# SCH_Bullseye_ESP32_2022-06-18.net
KiCad netlist of a schematic drawn in EasyEDA
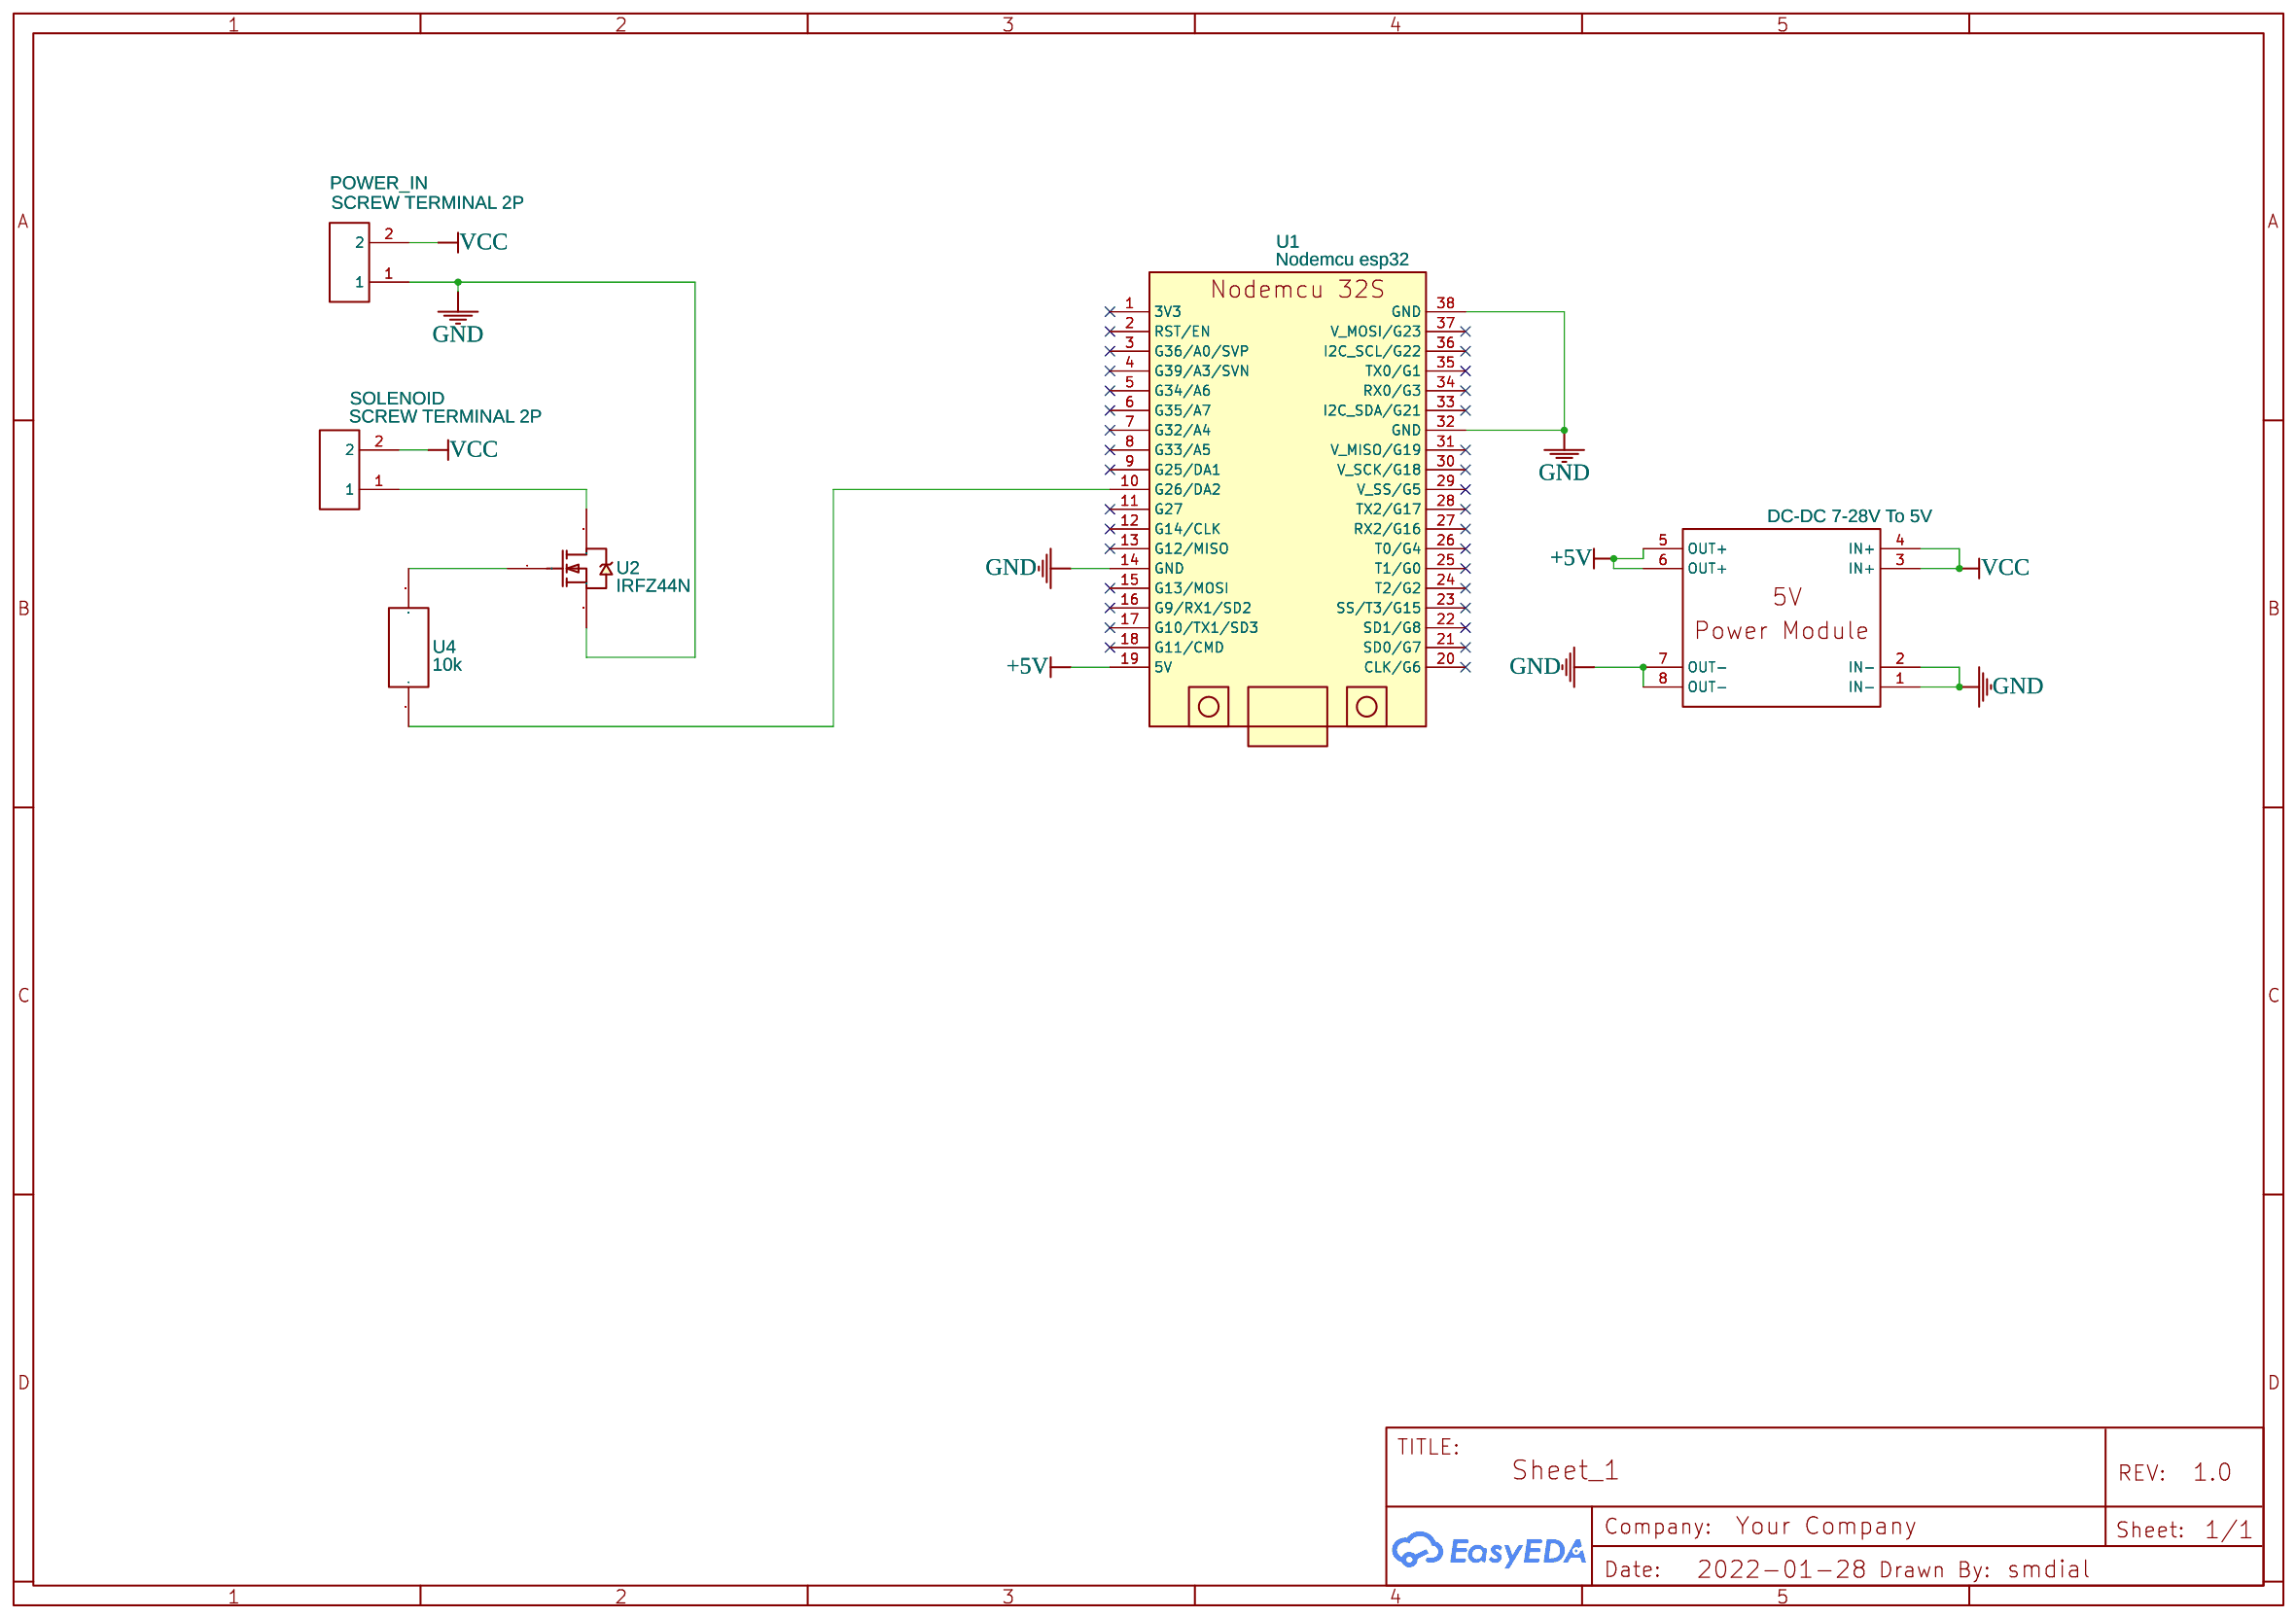
[diagram p0: schematic sheet]

(export (version "E")
  (design (tool "Eeschema 10.0.6"))
  (components
    (comp (ref "POWER_IN")
      (value "SCREW TERMINAL 2P")
      (fields (field (name "BOM_Manufacturer Part") "Screw terminal 2p"))
      (libsource (lib "") (part "SCREW TERMINAL 2P_1"))
    )
    (comp (ref "SOLENOID")
      (value "SCREW TERMINAL 2P")
      (fields (field (name "BOM_Manufacturer Part") "Screw terminal 2p"))
      (libsource (lib "") (part "SCREW TERMINAL 2P"))
    )
    (comp (ref "U1") (value "Nodemcu esp32") (libsource (lib "") (part "Nodemcu esp32")))
    (comp (ref "U2") (value "IRFZ44N") (libsource (lib "") (part "IRFZ44N")))
    (comp (ref "U3")
      (value "DC-DC 7-28V To 5V")
      (fields (field (name "BOM_Manufacturer Part") "DC-DC 7-28V To 5V Step Down Power Supply Module"))
      (libsource (lib "") (part "DC-DC 7-28V To 5V Step Down Power Supply Module"))
    )
    (comp (ref "U4") (value "10k") (libsource (lib "") (part "RESISTOR")))
  )
  (nets
    (net (code "1") (name "+5V") (class "Default")
      (node (ref "U1") (pin "19") (pinfunction "5V_19") (pintype "passive"))
      (node (ref "U3") (pin "5") (pinfunction "OUT+_5") (pintype "unspecified"))
      (node (ref "U3") (pin "6") (pinfunction "OUT+_6") (pintype "unspecified"))
    )
    (net (code "2") (name "GND") (class "Default")
      (node (ref "POWER_IN") (pin "1") (pinfunction "1_1") (pintype "unspecified"))
      (node (ref "U1") (pin "14") (pinfunction "GND_14") (pintype "passive"))
      (node (ref "U1") (pin "32") (pinfunction "GND_32") (pintype "passive"))
      (node (ref "U1") (pin "38") (pinfunction "GND_38") (pintype "passive"))
      (node (ref "U2") (pin "3") (pinfunction "S_3") (pintype "unspecified"))
      (node (ref "U3") (pin "1") (pinfunction "IN-_1") (pintype "unspecified"))
      (node (ref "U3") (pin "2") (pinfunction "IN-_2") (pintype "unspecified"))
      (node (ref "U3") (pin "7") (pinfunction "OUT-_7") (pintype "unspecified"))
      (node (ref "U3") (pin "8") (pinfunction "OUT-_8") (pintype "unspecified"))
    )
    (net (code "3") (name "Net-(U1-G26{slash}DA2)") (class "Default")
      (node (ref "U1") (pin "10") (pinfunction "G26/DA2_10") (pintype "bidirectional"))
      (node (ref "U4") (pin "1") (pinfunction "1_1") (pintype "unspecified"))
    )
    (net (code "4") (name "Net-(U2-D)") (class "Default")
      (node (ref "SOLENOID") (pin "1") (pinfunction "1_1") (pintype "unspecified"))
      (node (ref "U2") (pin "2") (pinfunction "D_2") (pintype "unspecified"))
    )
    (net (code "5") (name "Net-(U2-G)") (class "Default")
      (node (ref "U2") (pin "1") (pinfunction "G_1") (pintype "unspecified"))
      (node (ref "U4") (pin "2") (pinfunction "2_2") (pintype "unspecified"))
    )
    (net (code "6") (name "VCC") (class "Default")
      (node (ref "POWER_IN") (pin "2") (pinfunction "2_2") (pintype "unspecified"))
      (node (ref "SOLENOID") (pin "2") (pinfunction "2_2") (pintype "unspecified"))
      (node (ref "U3") (pin "3") (pinfunction "IN+_3") (pintype "unspecified"))
      (node (ref "U3") (pin "4") (pinfunction "IN+_4") (pintype "unspecified"))
    )
    (net (code "7") (name "unconnected-(U1-3V3-Pad1)") (class "Default")
      (node (ref "U1") (pin "1") (pinfunction "3V3_1") (pintype "passive+no_connect"))
    )
    (net (code "8") (name "unconnected-(U1-CLK{slash}G6-Pad20)") (class "Default")
      (node (ref "U1") (pin "20") (pinfunction "CLK/G6_20") (pintype "bidirectional+no_connect"))
    )
    (net (code "9") (name "unconnected-(U1-G9{slash}RX1{slash}SD2-Pad16)") (class "Default")
      (node (ref "U1") (pin "16") (pinfunction "G9/RX1/SD2_16") (pintype "bidirectional+no_connect"))
    )
    (net (code "10") (name "unconnected-(U1-G10{slash}TX1{slash}SD3-Pad17)") (class "Default")
      (node (ref "U1") (pin "17") (pinfunction "G10/TX1/SD3_17") (pintype "bidirectional+no_connect"))
    )
    (net (code "11") (name "unconnected-(U1-G11{slash}CMD-Pad18)") (class "Default")
      (node (ref "U1") (pin "18") (pinfunction "G11/CMD_18") (pintype "bidirectional+no_connect"))
    )
    (net (code "12") (name "unconnected-(U1-G12{slash}MISO-Pad13)") (class "Default")
      (node (ref "U1") (pin "13") (pinfunction "G12/MISO_13") (pintype "bidirectional+no_connect"))
    )
    (net (code "13") (name "unconnected-(U1-G13{slash}MOSI-Pad15)") (class "Default")
      (node (ref "U1") (pin "15") (pinfunction "G13/MOSI_15") (pintype "bidirectional+no_connect"))
    )
    (net (code "14") (name "unconnected-(U1-G14{slash}CLK-Pad12)") (class "Default")
      (node (ref "U1") (pin "12") (pinfunction "G14/CLK_12") (pintype "bidirectional+no_connect"))
    )
    (net (code "15") (name "unconnected-(U1-G25{slash}DA1-Pad9)") (class "Default")
      (node (ref "U1") (pin "9") (pinfunction "G25/DA1_9") (pintype "bidirectional+no_connect"))
    )
    (net (code "16") (name "unconnected-(U1-G27-Pad11)") (class "Default")
      (node (ref "U1") (pin "11") (pinfunction "G27_11") (pintype "bidirectional+no_connect"))
    )
    (net (code "17") (name "unconnected-(U1-G32{slash}A4-Pad7)") (class "Default")
      (node (ref "U1") (pin "7") (pinfunction "G32/A4_7") (pintype "bidirectional+no_connect"))
    )
    (net (code "18") (name "unconnected-(U1-G33{slash}A5-Pad8)") (class "Default")
      (node (ref "U1") (pin "8") (pinfunction "G33/A5_8") (pintype "bidirectional+no_connect"))
    )
    (net (code "19") (name "unconnected-(U1-G34{slash}A6-Pad5)") (class "Default")
      (node (ref "U1") (pin "5") (pinfunction "G34/A6_5") (pintype "bidirectional+no_connect"))
    )
    (net (code "20") (name "unconnected-(U1-G35{slash}A7-Pad6)") (class "Default")
      (node (ref "U1") (pin "6") (pinfunction "G35/A7_6") (pintype "bidirectional+no_connect"))
    )
    (net (code "21") (name "unconnected-(U1-G36{slash}A0{slash}SVP-Pad3)") (class "Default")
      (node (ref "U1") (pin "3") (pinfunction "G36/A0/SVP_3") (pintype "bidirectional+no_connect"))
    )
    (net (code "22") (name "unconnected-(U1-G39{slash}A3{slash}SVN-Pad4)") (class "Default")
      (node (ref "U1") (pin "4") (pinfunction "G39/A3/SVN_4") (pintype "bidirectional+no_connect"))
    )
    (net (code "23") (name "unconnected-(U1-I2C_SCL{slash}G22-Pad36)") (class "Default")
      (node (ref "U1") (pin "36") (pinfunction "I2C_SCL/G22_36") (pintype "bidirectional+no_connect"))
    )
    (net (code "24") (name "unconnected-(U1-I2C_SDA{slash}G21-Pad33)") (class "Default")
      (node (ref "U1") (pin "33") (pinfunction "I2C_SDA/G21_33") (pintype "bidirectional+no_connect"))
    )
    (net (code "25") (name "unconnected-(U1-RST{slash}EN-Pad2)") (class "Default")
      (node (ref "U1") (pin "2") (pinfunction "RST/EN_2") (pintype "bidirectional+no_connect"))
    )
    (net (code "26") (name "unconnected-(U1-RX0{slash}G3-Pad34)") (class "Default")
      (node (ref "U1") (pin "34") (pinfunction "RX0/G3_34") (pintype "bidirectional+no_connect"))
    )
    (net (code "27") (name "unconnected-(U1-RX2{slash}G16-Pad27)") (class "Default")
      (node (ref "U1") (pin "27") (pinfunction "RX2/G16_27") (pintype "bidirectional+no_connect"))
    )
    (net (code "28") (name "unconnected-(U1-SD0{slash}G7-Pad21)") (class "Default")
      (node (ref "U1") (pin "21") (pinfunction "SD0/G7_21") (pintype "bidirectional+no_connect"))
    )
    (net (code "29") (name "unconnected-(U1-SD1{slash}G8-Pad22)") (class "Default")
      (node (ref "U1") (pin "22") (pinfunction "SD1/G8_22") (pintype "bidirectional+no_connect"))
    )
    (net (code "30") (name "unconnected-(U1-SS{slash}T3{slash}G15-Pad23)") (class "Default")
      (node (ref "U1") (pin "23") (pinfunction "SS/T3/G15_23") (pintype "bidirectional+no_connect"))
    )
    (net (code "31") (name "unconnected-(U1-T0{slash}G4-Pad26)") (class "Default")
      (node (ref "U1") (pin "26") (pinfunction "T0/G4_26") (pintype "bidirectional+no_connect"))
    )
    (net (code "32") (name "unconnected-(U1-T1{slash}G0-Pad25)") (class "Default")
      (node (ref "U1") (pin "25") (pinfunction "T1/G0_25") (pintype "bidirectional+no_connect"))
    )
    (net (code "33") (name "unconnected-(U1-T2{slash}G2-Pad24)") (class "Default")
      (node (ref "U1") (pin "24") (pinfunction "T2/G2_24") (pintype "bidirectional+no_connect"))
    )
    (net (code "34") (name "unconnected-(U1-TX0{slash}G1-Pad35)") (class "Default")
      (node (ref "U1") (pin "35") (pinfunction "TX0/G1_35") (pintype "bidirectional+no_connect"))
    )
    (net (code "35") (name "unconnected-(U1-TX2{slash}G17-Pad28)") (class "Default")
      (node (ref "U1") (pin "28") (pinfunction "TX2/G17_28") (pintype "bidirectional+no_connect"))
    )
    (net (code "36") (name "unconnected-(U1-V_MISO{slash}G19-Pad31)") (class "Default")
      (node (ref "U1") (pin "31") (pinfunction "V_MISO/G19_31") (pintype "bidirectional+no_connect"))
    )
    (net (code "37") (name "unconnected-(U1-V_MOSI{slash}G23-Pad37)") (class "Default")
      (node (ref "U1") (pin "37") (pinfunction "V_MOSI/G23_37") (pintype "bidirectional+no_connect"))
    )
    (net (code "38") (name "unconnected-(U1-V_SCK{slash}G18-Pad30)") (class "Default")
      (node (ref "U1") (pin "30") (pinfunction "V_SCK/G18_30") (pintype "bidirectional+no_connect"))
    )
    (net (code "39") (name "unconnected-(U1-V_SS{slash}G5-Pad29)") (class "Default")
      (node (ref "U1") (pin "29") (pinfunction "V_SS/G5_29") (pintype "bidirectional+no_connect"))
    )
  )
)
